# SensWear_MPU.net
KiCad netlist of a schematic drawn in Altium Designer
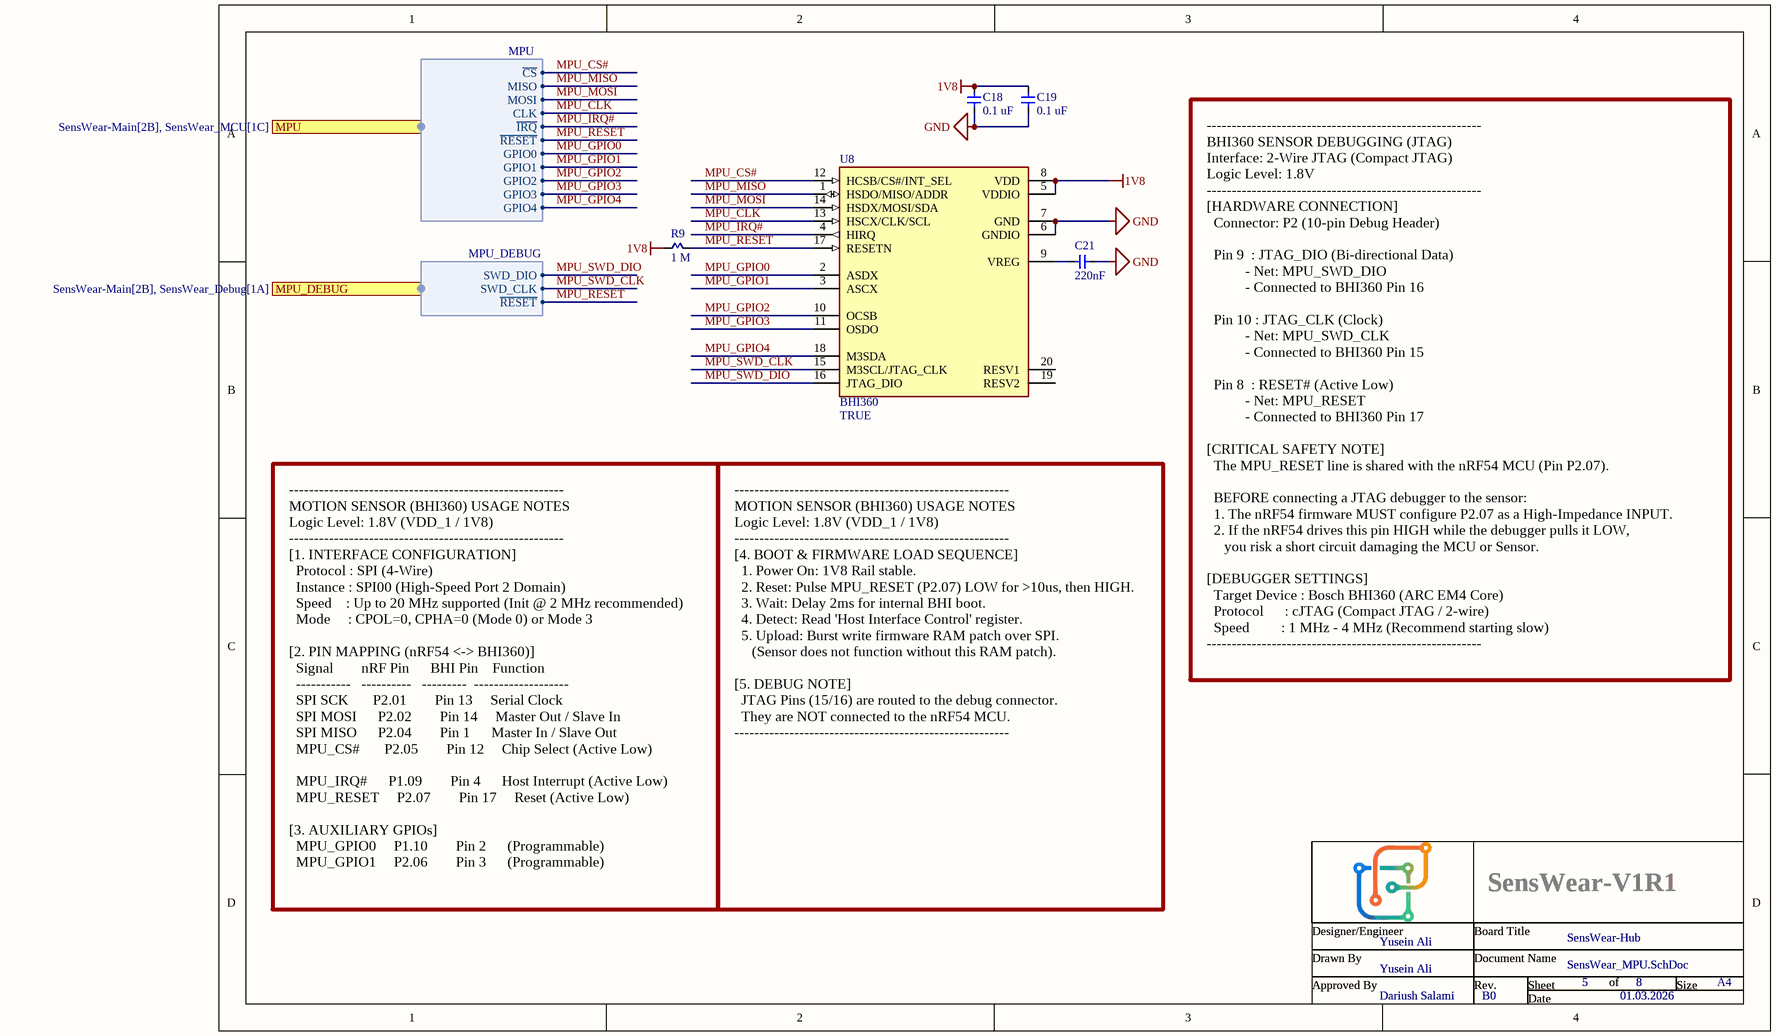
[diagram p0: SensWear_MPU.SchDoc]

(export (version "E")
  (design (tool "Eeschema 10.0.6"))
  (components
    (comp (ref "C18")
      (value "0.1 uF")
      (footprint "CAPC1005X05N")
      (description "CAP CER 0.1UF 16V X5R 0402")
      (fields
        (field (name "MANUFACTURER") "Murata Electronics")
        (field (name "MANUFACTURER PART NUMBER") "GRM155R61C104KA88D")
      )
      (libsource (lib "SensWearComponents") (part "GRM155R61C104KA88D__2"))
    )
    (comp (ref "C19")
      (value "0.1 uF")
      (footprint "CAPC1005X05N")
      (description "CAP CER 0.1UF 16V X5R 0402")
      (fields
        (field (name "MANUFACTURER") "Murata Electronics")
        (field (name "MANUFACTURER PART NUMBER") "GRM155R61C104KA88D")
      )
      (libsource (lib "SensWearComponents") (part "GRM155R61C104KA88D__2"))
    )
    (comp (ref "C21")
      (value "220nF")
      (footprint "CAPC1005X05N")
      (description "CAP CER 0.22UF 16V X5R 0402")
      (fields
        (field (name "MANUFACTURER") "Murata")
        (field (name "MANUFACTURER PART NUMBER") "GRM155R61C224KA12D")
      )
      (libsource (lib "SensWearComponents") (part "GRM155R61C224KA12D"))
    )
    (comp (ref "R9")
      (value "1 M")
      (footprint "RESC1005X04N")
      (description "RES SMD 1M OHM 1% 1/10W 0402")
      (fields
        (field (name "MANUFACTURER") "Panasonic Electronic Components")
        (field (name "MANUFACTURER PART NUMBER") "ERJ-2RKF1004X")
      )
      (libsource (lib "SensWearComponents") (part "ERJ-2RKF1004X"))
    )
    (comp (ref "U8")
      (value "BHI360")
      (footprint "BHI360")
      (description "Programmable smart sensor combining accelerometer, gyroscope and fusion software")
      (fields (field (name "MANUFACTURER") "Bosch Tools") (field (name "CHECKED") "TRUE"))
      (libsource (lib "SensWearComponents") (part "BHI360"))
    )
  )
  (nets
    (net (code "3") (name "/MPU_CLK") (class "Default")
      (node (ref "U8") (pin "13") (pinfunction "HSCX/CLK/SCL_13") (pintype "input"))
    )
    (net (code "4") (name "/MPU_CS#") (class "Default")
      (node (ref "U8") (pin "12") (pinfunction "HCSB/CS#/INT_SEL_12") (pintype "input"))
    )
    (net (code "5") (name "/MPU_GPIO0") (class "Default")
      (node (ref "U8") (pin "2") (pinfunction "ASDX_2") (pintype "passive"))
    )
    (net (code "6") (name "/MPU_GPIO1") (class "Default")
      (node (ref "U8") (pin "3") (pinfunction "ASCX_3") (pintype "passive"))
    )
    (net (code "7") (name "/MPU_GPIO2") (class "Default")
      (node (ref "U8") (pin "10") (pinfunction "OCSB_10") (pintype "passive"))
    )
    (net (code "8") (name "/MPU_GPIO3") (class "Default")
      (node (ref "U8") (pin "11") (pinfunction "OSDO_11") (pintype "passive"))
    )
    (net (code "9") (name "/MPU_GPIO4") (class "Default")
      (node (ref "U8") (pin "18") (pinfunction "M3SDA_18") (pintype "passive"))
    )
    (net (code "10") (name "/MPU_IRQ#") (class "Default")
      (node (ref "U8") (pin "4") (pinfunction "HIRQ_4") (pintype "output"))
    )
    (net (code "11") (name "/MPU_MISO") (class "Default")
      (node (ref "U8") (pin "1") (pinfunction "HSDO/MISO/ADDR_1") (pintype "bidirectional"))
    )
    (net (code "12") (name "/MPU_MOSI") (class "Default")
      (node (ref "U8") (pin "14") (pinfunction "HSDX/MOSI/SDA_14") (pintype "input"))
    )
    (net (code "13") (name "/MPU_SWD_CLK") (class "Default")
      (node (ref "U8") (pin "15") (pinfunction "M3SCL/JTAG_CLK_15") (pintype "passive"))
    )
    (net (code "14") (name "/MPU_SWD_DIO") (class "Default")
      (node (ref "U8") (pin "16") (pinfunction "JTAG_DIO_16") (pintype "passive"))
    )
    (net (code "15") (name "/MPU_~{RESET}") (class "Default")
      (node (ref "R9") (pin "2") (pinfunction "2_2") (pintype "passive"))
      (node (ref "U8") (pin "17") (pinfunction "RESETN_17") (pintype "input"))
    )
    (net (code "18") (name "1V8") (class "Default")
      (node (ref "C18") (pin "2") (pinfunction "2_2") (pintype "passive"))
      (node (ref "C19") (pin "2") (pinfunction "2_2") (pintype "passive"))
      (node (ref "R9") (pin "1") (pinfunction "1_1") (pintype "passive"))
      (node (ref "U8") (pin "5") (pinfunction "VDDIO_5") (pintype "passive"))
      (node (ref "U8") (pin "8") (pinfunction "VDD_8") (pintype "passive"))
    )
    (net (code "19") (name "GND") (class "Default")
      (node (ref "C18") (pin "1") (pinfunction "1_1") (pintype "passive"))
      (node (ref "C19") (pin "1") (pinfunction "1_1") (pintype "passive"))
      (node (ref "C21") (pin "2") (pinfunction "2_2") (pintype "passive"))
      (node (ref "U8") (pin "6") (pinfunction "GNDIO_6") (pintype "passive"))
      (node (ref "U8") (pin "7") (pinfunction "GND_7") (pintype "passive"))
    )
    (net (code "20") (name "Net-(U8-VREG)") (class "Default")
      (node (ref "C21") (pin "1") (pinfunction "1_1") (pintype "passive"))
      (node (ref "U8") (pin "9") (pinfunction "VREG_9") (pintype "passive"))
    )
    (net (code "21") (name "unconnected-(U8-RESV1-Pad20)") (class "Default")
      (node (ref "U8") (pin "20") (pinfunction "RESV1_20") (pintype "passive"))
    )
    (net (code "22") (name "unconnected-(U8-RESV2-Pad19)") (class "Default")
      (node (ref "U8") (pin "19") (pinfunction "RESV2_19") (pintype "passive"))
    )
  )
)
